# Toplevel.net
KiCad netlist of a schematic drawn in Altium Designer
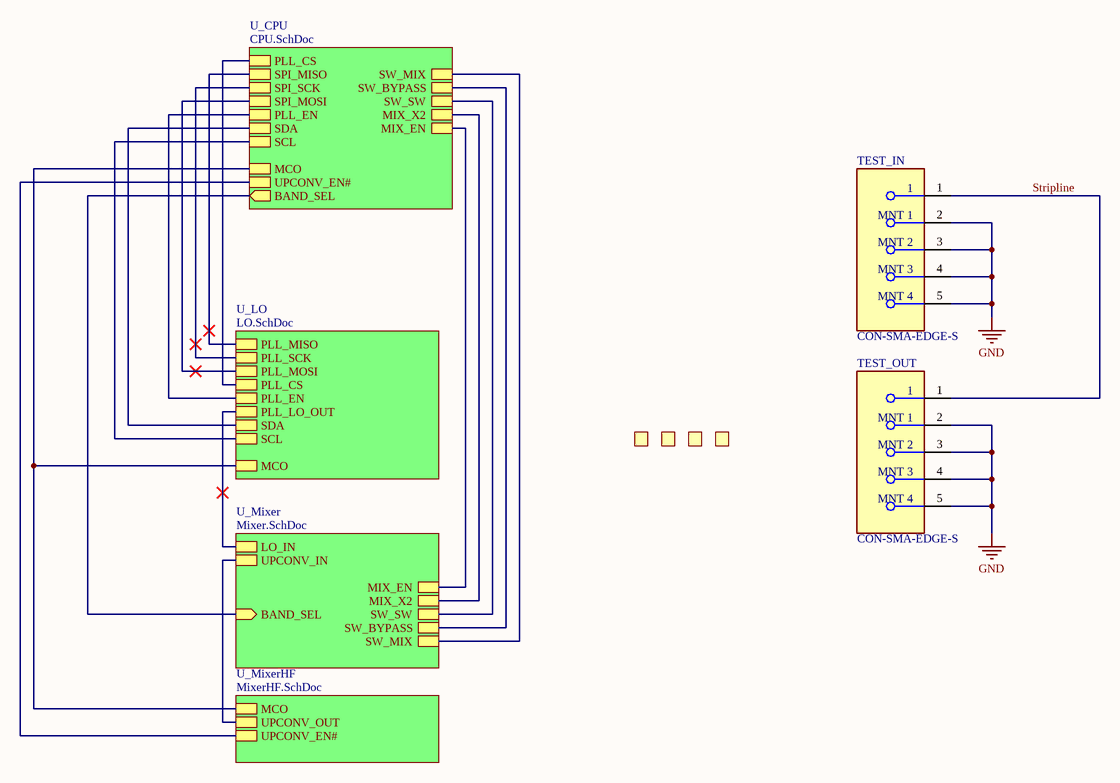
[diagram p0: Toplevel.SchDoc]

(export (version "E")
  (design (tool "Eeschema 10.0.6"))
  (components
    (comp (ref "H1")
      (value "MOUNTHOLE_3MM")
      (footprint "MOUNT_3MM")
      (libsource (lib "library") (part "MOUNTHOLE_3MM"))
    )
    (comp (ref "H2")
      (value "MOUNTHOLE_3MM")
      (footprint "MOUNT_3MM")
      (libsource (lib "library") (part "MOUNTHOLE_3MM"))
    )
    (comp (ref "H3")
      (value "MOUNTHOLE_3MM")
      (footprint "MOUNT_3MM")
      (libsource (lib "library") (part "MOUNTHOLE_3MM"))
    )
    (comp (ref "H4")
      (value "MOUNTHOLE_3MM")
      (footprint "MOUNT_3MM")
      (libsource (lib "library") (part "MOUNTHOLE_3MM"))
    )
    (comp (ref "TEST_IN")
      (value "CON-SMA-EDGE-S")
      (footprint "FP-CON-SMA-EDGE-S-MFG")
      (description "CONN SMA JACK STR EDGE MNT")
      (fields
        (field (name "OCTOPART") "https://octopart.com/con-sma-edge-s-rf+solutions-70967450")
        (field (name "MANUFACTURER") "RF Solutions Ltd.")
      )
      (libsource (lib "Altium Content Vault") (part "a163d97a771fcdd2fd1f1a9264c171f"))
    )
    (comp (ref "TEST_OUT")
      (value "CON-SMA-EDGE-S")
      (footprint "FP-CON-SMA-EDGE-S-MFG")
      (description "CONN SMA JACK STR EDGE MNT")
      (fields
        (field (name "OCTOPART") "https://octopart.com/con-sma-edge-s-rf+solutions-70967450")
        (field (name "MANUFACTURER") "RF Solutions Ltd.")
      )
      (libsource (lib "Altium Content Vault") (part "a163d97a771fcdd2fd1f1a9264c171f"))
    )
  )
  (nets
    (net (code "16") (name "/Stripline") (class "Default")
      (node (ref "TEST_IN") (pin "1") (pinfunction "1_1") (pintype "passive"))
      (node (ref "TEST_OUT") (pin "1") (pinfunction "1_1") (pintype "passive"))
    )
    (net (code "19") (name "GND") (class "Default")
      (node (ref "TEST_IN") (pin "2") (pinfunction "MNT_1_2") (pintype "passive"))
      (node (ref "TEST_IN") (pin "3") (pinfunction "MNT_2_3") (pintype "passive"))
      (node (ref "TEST_IN") (pin "4") (pinfunction "MNT_3_4") (pintype "passive"))
      (node (ref "TEST_IN") (pin "5") (pinfunction "MNT_4_5") (pintype "passive"))
      (node (ref "TEST_OUT") (pin "2") (pinfunction "MNT_1_2") (pintype "passive"))
      (node (ref "TEST_OUT") (pin "3") (pinfunction "MNT_2_3") (pintype "passive"))
      (node (ref "TEST_OUT") (pin "4") (pinfunction "MNT_3_4") (pintype "passive"))
      (node (ref "TEST_OUT") (pin "5") (pinfunction "MNT_4_5") (pintype "passive"))
    )
  )
)
